# M661X.net
KiCad netlist of a schematic drawn in EAGLE
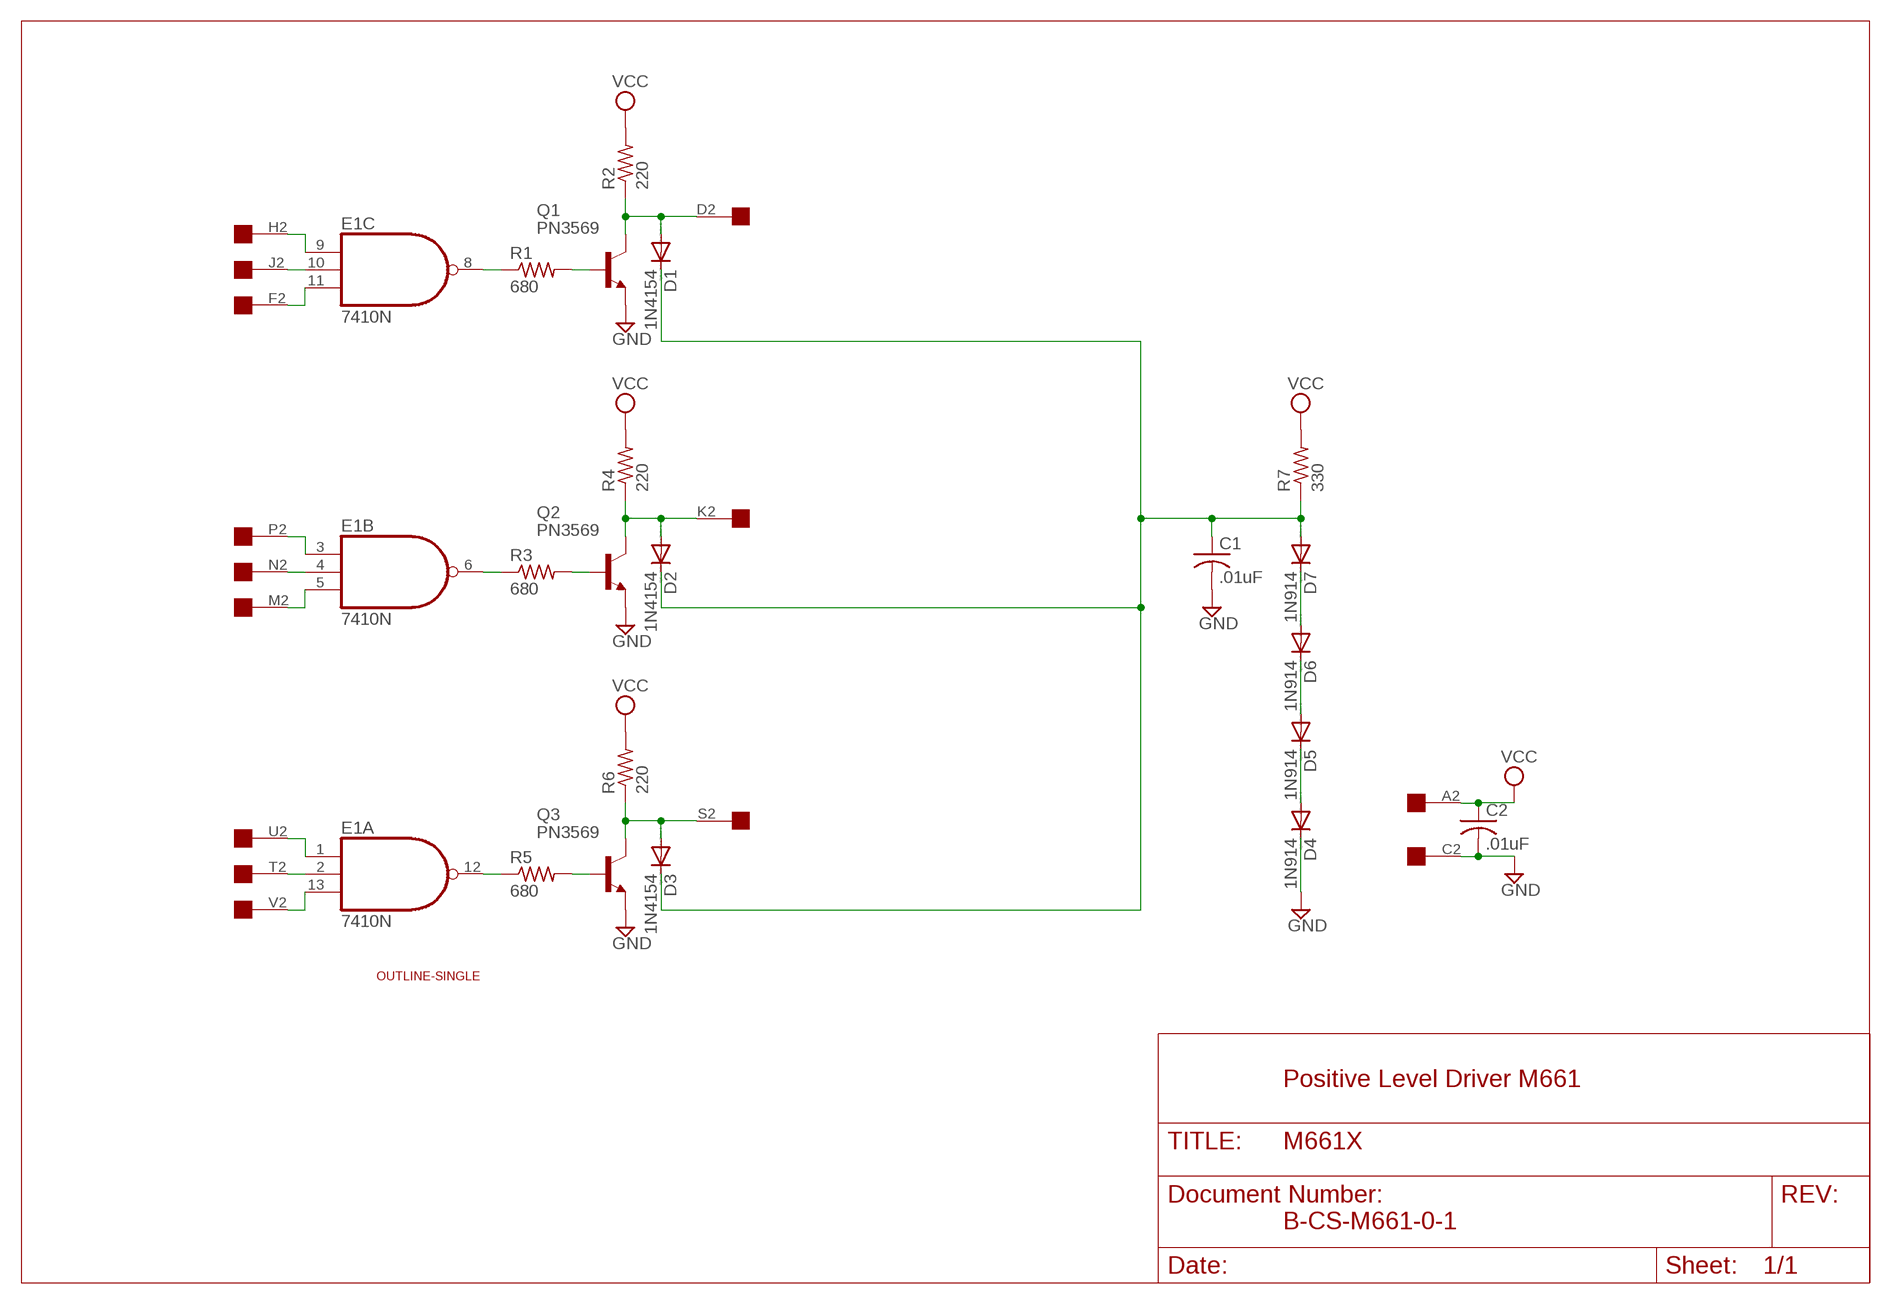
[diagram p0: schematic, sheet 1]

(export (version "E")
  (design (tool "Eeschema 10.0.6"))
  (components
    (comp (ref "C1")
      (value ".01uF")
      (footprint "eagle-import:C050-025X075")
      (libsource (lib "eagle-import") (part "C-US050-025X075"))
    )
    (comp (ref "C2")
      (value ".01uF")
      (footprint "eagle-import:C050-025X075")
      (libsource (lib "eagle-import") (part "C-US050-025X075"))
    )
    (comp (ref "D1")
      (value "1N4154")
      (footprint "eagle-import:DO35-10")
      (libsource (lib "eagle-import") (part "1N4148DO35-10"))
    )
    (comp (ref "D2")
      (value "1N4154")
      (footprint "eagle-import:DO35-10")
      (libsource (lib "eagle-import") (part "1N4148DO35-10"))
    )
    (comp (ref "D3")
      (value "1N4154")
      (footprint "eagle-import:DO35-10")
      (libsource (lib "eagle-import") (part "1N4148DO35-10"))
    )
    (comp (ref "D4")
      (value "1N914")
      (footprint "eagle-import:DO35-10")
      (libsource (lib "eagle-import") (part "1N4148DO35-10"))
    )
    (comp (ref "D5")
      (value "1N914")
      (footprint "eagle-import:DO35-10")
      (libsource (lib "eagle-import") (part "1N4148DO35-10"))
    )
    (comp (ref "D6")
      (value "1N914")
      (footprint "eagle-import:DO35-10")
      (libsource (lib "eagle-import") (part "1N4148DO35-10"))
    )
    (comp (ref "D7")
      (value "1N914")
      (footprint "eagle-import:DO35-10")
      (libsource (lib "eagle-import") (part "1N4148DO35-10"))
    )
    (comp (ref "E1")
      (value "7410N")
      (footprint "eagle-import:DIL14")
      (libsource (lib "eagle-import") (part "7410N"))
    )
    (comp (ref "Q1")
      (value "PN3569")
      (footprint "eagle-import:TO5")
      (libsource (lib "eagle-import") (part "2N2219"))
    )
    (comp (ref "Q2")
      (value "PN3569")
      (footprint "eagle-import:TO5")
      (libsource (lib "eagle-import") (part "2N2219"))
    )
    (comp (ref "Q3")
      (value "PN3569")
      (footprint "eagle-import:TO5")
      (libsource (lib "eagle-import") (part "2N2219"))
    )
    (comp (ref "R1")
      (value "680")
      (footprint "eagle-import:0207_10")
      (libsource (lib "eagle-import") (part "R-US_0207/10"))
    )
    (comp (ref "R2")
      (value "220")
      (footprint "eagle-import:0207_10")
      (libsource (lib "eagle-import") (part "R-US_0207/10"))
    )
    (comp (ref "R3")
      (value "680")
      (footprint "eagle-import:0207_10")
      (libsource (lib "eagle-import") (part "R-US_0207/10"))
    )
    (comp (ref "R4")
      (value "220")
      (footprint "eagle-import:0207_10")
      (libsource (lib "eagle-import") (part "R-US_0207/10"))
    )
    (comp (ref "R5")
      (value "680")
      (footprint "eagle-import:0207_10")
      (libsource (lib "eagle-import") (part "R-US_0207/10"))
    )
    (comp (ref "R6")
      (value "220")
      (footprint "eagle-import:0207_10")
      (libsource (lib "eagle-import") (part "R-US_0207/10"))
    )
    (comp (ref "R7")
      (value "330")
      (footprint "eagle-import:0207_10")
      (libsource (lib "eagle-import") (part "R-US_0207/10"))
    )
    (comp (ref "U$1")
      (value "OUTLINE-SINGLE")
      (footprint "eagle-import:SINGLE")
      (libsource (lib "eagle-import") (part "OUTLINE-SINGLE"))
    )
    (comp (ref "U$3")
      (value "EDGE-1")
      (footprint "eagle-import:EDGE-CON1")
      (libsource (lib "eagle-import") (part "EDGE-1"))
    )
  )
  (nets
    (net (code "1") (name "GND") (class "Default")
      (node (ref "C1") (pin "2") (pinfunction "2_2") (pintype "passive"))
      (node (ref "C2") (pin "2") (pinfunction "2_2") (pintype "passive"))
      (node (ref "D4") (pin "C") (pinfunction "C_C") (pintype "passive"))
      (node (ref "Q1") (pin "1") (pinfunction "E_1") (pintype "passive"))
      (node (ref "Q2") (pin "1") (pinfunction "E_1") (pintype "passive"))
      (node (ref "Q3") (pin "1") (pinfunction "E_1") (pintype "passive"))
      (node (ref "U$3") (pin "C2") (pinfunction "1_C2") (pintype "bidirectional"))
    )
    (net (code "2") (name "Net-(C1-Pad1)") (class "Default")
      (node (ref "C1") (pin "1") (pinfunction "1_1") (pintype "passive"))
      (node (ref "D1") (pin "C") (pinfunction "C_C") (pintype "passive"))
      (node (ref "D2") (pin "C") (pinfunction "C_C") (pintype "passive"))
      (node (ref "D3") (pin "C") (pinfunction "C_C") (pintype "passive"))
      (node (ref "D7") (pin "A") (pinfunction "A_A") (pintype "passive"))
      (node (ref "R7") (pin "1") (pinfunction "1_1") (pintype "passive"))
    )
    (net (code "3") (name "Net-(D4-PadA)") (class "Default")
      (node (ref "D4") (pin "A") (pinfunction "A_A") (pintype "passive"))
      (node (ref "D5") (pin "C") (pinfunction "C_C") (pintype "passive"))
    )
    (net (code "4") (name "Net-(D5-PadA)") (class "Default")
      (node (ref "D5") (pin "A") (pinfunction "A_A") (pintype "passive"))
      (node (ref "D6") (pin "C") (pinfunction "C_C") (pintype "passive"))
    )
    (net (code "5") (name "Net-(D6-PadA)") (class "Default")
      (node (ref "D6") (pin "A") (pinfunction "A_A") (pintype "passive"))
      (node (ref "D7") (pin "C") (pinfunction "C_C") (pintype "passive"))
    )
    (net (code "6") (name "Net-(E1A-I0)") (class "Default")
      (node (ref "E1") (pin "1") (pinfunction "I0_1") (pintype "input"))
      (node (ref "U$3") (pin "U2") (pinfunction "1_U2") (pintype "bidirectional"))
    )
    (net (code "7") (name "Net-(E1A-I1)") (class "Default")
      (node (ref "E1") (pin "2") (pinfunction "I1_2") (pintype "input"))
      (node (ref "U$3") (pin "T2") (pinfunction "1_T2") (pintype "bidirectional"))
    )
    (net (code "8") (name "Net-(E1A-I2)") (class "Default")
      (node (ref "E1") (pin "13") (pinfunction "I2_13") (pintype "input"))
      (node (ref "U$3") (pin "V2") (pinfunction "1_V2") (pintype "bidirectional"))
    )
    (net (code "9") (name "Net-(E1A-O)") (class "Default")
      (node (ref "E1") (pin "12") (pinfunction "O_12") (pintype "output"))
      (node (ref "R5") (pin "1") (pinfunction "1_1") (pintype "passive"))
    )
    (net (code "10") (name "Net-(E1B-I0)") (class "Default")
      (node (ref "E1") (pin "3") (pinfunction "I0_3") (pintype "input"))
      (node (ref "U$3") (pin "P2") (pinfunction "1_P2") (pintype "bidirectional"))
    )
    (net (code "11") (name "Net-(E1B-I1)") (class "Default")
      (node (ref "E1") (pin "4") (pinfunction "I1_4") (pintype "input"))
      (node (ref "U$3") (pin "N2") (pinfunction "1_N2") (pintype "bidirectional"))
    )
    (net (code "12") (name "Net-(E1B-I2)") (class "Default")
      (node (ref "E1") (pin "5") (pinfunction "I2_5") (pintype "input"))
      (node (ref "U$3") (pin "M2") (pinfunction "1_M2") (pintype "bidirectional"))
    )
    (net (code "13") (name "Net-(E1B-O)") (class "Default")
      (node (ref "E1") (pin "6") (pinfunction "O_6") (pintype "output"))
      (node (ref "R3") (pin "1") (pinfunction "1_1") (pintype "passive"))
    )
    (net (code "14") (name "Net-(E1C-I0)") (class "Default")
      (node (ref "E1") (pin "9") (pinfunction "I0_9") (pintype "input"))
      (node (ref "U$3") (pin "H2") (pinfunction "1_H2") (pintype "bidirectional"))
    )
    (net (code "15") (name "Net-(E1C-I1)") (class "Default")
      (node (ref "E1") (pin "10") (pinfunction "I1_10") (pintype "input"))
      (node (ref "U$3") (pin "J2") (pinfunction "1_J2") (pintype "bidirectional"))
    )
    (net (code "16") (name "Net-(E1C-I2)") (class "Default")
      (node (ref "E1") (pin "11") (pinfunction "I2_11") (pintype "input"))
      (node (ref "U$3") (pin "F2") (pinfunction "1_F2") (pintype "bidirectional"))
    )
    (net (code "17") (name "Net-(E1C-O)") (class "Default")
      (node (ref "E1") (pin "8") (pinfunction "O_8") (pintype "output"))
      (node (ref "R1") (pin "1") (pinfunction "1_1") (pintype "passive"))
    )
    (net (code "18") (name "Net-(Q1-B)") (class "Default")
      (node (ref "Q1") (pin "2") (pinfunction "B_2") (pintype "passive"))
      (node (ref "R1") (pin "2") (pinfunction "2_2") (pintype "passive"))
    )
    (net (code "19") (name "Net-(Q1-C)") (class "Default")
      (node (ref "D1") (pin "A") (pinfunction "A_A") (pintype "passive"))
      (node (ref "Q1") (pin "3") (pinfunction "C_3") (pintype "passive"))
      (node (ref "R2") (pin "1") (pinfunction "1_1") (pintype "passive"))
      (node (ref "U$3") (pin "D2") (pinfunction "1_D2") (pintype "bidirectional"))
    )
    (net (code "20") (name "Net-(Q2-B)") (class "Default")
      (node (ref "Q2") (pin "2") (pinfunction "B_2") (pintype "passive"))
      (node (ref "R3") (pin "2") (pinfunction "2_2") (pintype "passive"))
    )
    (net (code "21") (name "Net-(Q2-C)") (class "Default")
      (node (ref "D2") (pin "A") (pinfunction "A_A") (pintype "passive"))
      (node (ref "Q2") (pin "3") (pinfunction "C_3") (pintype "passive"))
      (node (ref "R4") (pin "1") (pinfunction "1_1") (pintype "passive"))
      (node (ref "U$3") (pin "K2") (pinfunction "1_K2") (pintype "bidirectional"))
    )
    (net (code "22") (name "Net-(Q3-B)") (class "Default")
      (node (ref "Q3") (pin "2") (pinfunction "B_2") (pintype "passive"))
      (node (ref "R5") (pin "2") (pinfunction "2_2") (pintype "passive"))
    )
    (net (code "23") (name "Net-(Q3-C)") (class "Default")
      (node (ref "D3") (pin "A") (pinfunction "A_A") (pintype "passive"))
      (node (ref "Q3") (pin "3") (pinfunction "C_3") (pintype "passive"))
      (node (ref "R6") (pin "1") (pinfunction "1_1") (pintype "passive"))
      (node (ref "U$3") (pin "S2") (pinfunction "1_S2") (pintype "bidirectional"))
    )
    (net (code "24") (name "VCC") (class "Default")
      (node (ref "C2") (pin "1") (pinfunction "1_1") (pintype "passive"))
      (node (ref "R2") (pin "2") (pinfunction "2_2") (pintype "passive"))
      (node (ref "R4") (pin "2") (pinfunction "2_2") (pintype "passive"))
      (node (ref "R6") (pin "2") (pinfunction "2_2") (pintype "passive"))
      (node (ref "R7") (pin "2") (pinfunction "2_2") (pintype "passive"))
      (node (ref "U$3") (pin "A2") (pinfunction "1_A2") (pintype "bidirectional"))
    )
  )
)
